# I2C_Multiplexer.net
KiCad netlist of a schematic drawn in Altium Designer
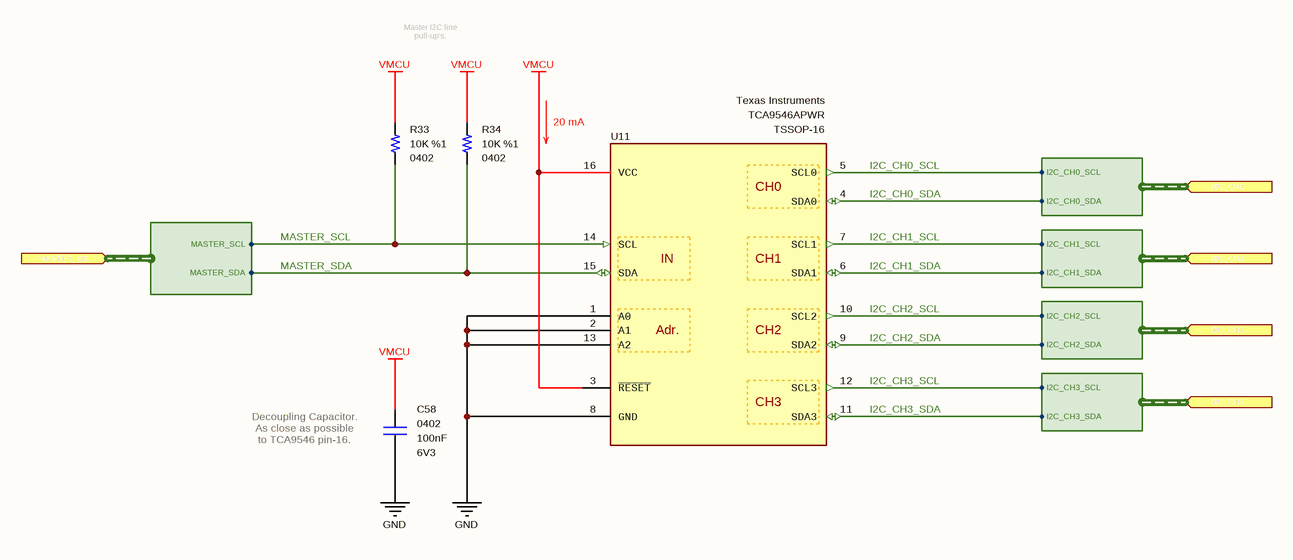
[diagram p0: I2C Multiplexer.SchDoc]

(export (version "E")
  (design (tool "Eeschema 10.0.6"))
  (components
    (comp (ref "C58")
      (value "100nF")
      (footprint "CAPACITOR_0402")
      (description "Capacitor - 100nF [0402-6V3] (Ceramic)")
      (fields
        (field (name "TOLERANCE") "%10")
        (field (name "CASE") "0402")
        (field (name "VOLTAGE") "6V3")
        (field (name "MANUFACTURER PART NUMBER") "04026D104KAT4A")
      )
      (libsource (lib "Ovoo_Library") (part "Capacitor - 100nF [0402-6V3]"))
    )
    (comp (ref "R33")
      (value "10K")
      (footprint "RESISTOR_0402")
      (description "Thick Film Resistors - SMD 1/16 W 10 Kohms 1%")
      (fields
        (field (name "TOLERANCE") "%1")
        (field (name "CASE") "0402")
        (field (name "MANUFACTURER PART NUMBER") "CRCW040210K0FKED")
        (field (name "MOUSER PART NUMBER") "71-CRCW0402-10K-E3")
      )
      (libsource (lib "Ovoo_Library") (part "Resistor - 10K"))
    )
    (comp (ref "R34")
      (value "10K")
      (footprint "RESISTOR_0402")
      (description "Thick Film Resistors - SMD 1/16 W 10 Kohms 1%")
      (fields
        (field (name "TOLERANCE") "%1")
        (field (name "CASE") "0402")
        (field (name "MANUFACTURER PART NUMBER") "CRCW040210K0FKED")
        (field (name "MOUSER PART NUMBER") "71-CRCW0402-10K-E3")
      )
      (libsource (lib "Ovoo_Library") (part "Resistor - 10K"))
    )
    (comp (ref "U11")
      (value "I2C Switch IC")
      (footprint "TSSOP-16")
      (description "Switch ICs - Various 4-Channel I2C and SMBus")
      (fields
        (field (name "MOUSER PART NUMBER") "595-TCA9546APWR")
        (field (name "CASE") "TSSOP-16")
        (field (name "MANUFACTURER PART NUMBER") "TCA9546APWR")
        (field (name "MANUFACTURER NAME") "Texas Instruments")
      )
      (libsource (lib "Ovoo_Library") (part "IC - TCA9546APWR"))
    )
  )
  (nets
    (net (code "6") (name "/I2C_CH0_SCL") (class "Default")
      (node (ref "U11") (pin "5") (pinfunction "SCL0_5") (pintype "output"))
    )
    (net (code "7") (name "/I2C_CH0_SDA") (class "Default")
      (node (ref "U11") (pin "4") (pinfunction "SDA0_4") (pintype "bidirectional"))
    )
    (net (code "8") (name "/I2C_CH1_SCL") (class "Default")
      (node (ref "U11") (pin "7") (pinfunction "SCL1_7") (pintype "output"))
    )
    (net (code "9") (name "/I2C_CH1_SDA") (class "Default")
      (node (ref "U11") (pin "6") (pinfunction "SDA1_6") (pintype "bidirectional"))
    )
    (net (code "10") (name "/I2C_CH2_SCL") (class "Default")
      (node (ref "U11") (pin "10") (pinfunction "SCL2_10") (pintype "output"))
    )
    (net (code "11") (name "/I2C_CH2_SDA") (class "Default")
      (node (ref "U11") (pin "9") (pinfunction "SDA2_9") (pintype "bidirectional"))
    )
    (net (code "12") (name "/I2C_CH3_SCL") (class "Default")
      (node (ref "U11") (pin "12") (pinfunction "SCL3_12") (pintype "output"))
    )
    (net (code "13") (name "/I2C_CH3_SDA") (class "Default")
      (node (ref "U11") (pin "11") (pinfunction "SDA3_11") (pintype "bidirectional"))
    )
    (net (code "14") (name "/MASTER_SCL") (class "Default")
      (node (ref "R33") (pin "1") (pinfunction "1_1") (pintype "passive"))
      (node (ref "U11") (pin "14") (pinfunction "SCL_14") (pintype "input"))
    )
    (net (code "15") (name "/MASTER_SDA") (class "Default")
      (node (ref "R34") (pin "1") (pinfunction "1_1") (pintype "passive"))
      (node (ref "U11") (pin "15") (pinfunction "SDA_15") (pintype "bidirectional"))
    )
    (net (code "21") (name "GND") (class "Default")
      (node (ref "C58") (pin "1") (pinfunction "1_1") (pintype "passive"))
      (node (ref "U11") (pin "1") (pinfunction "A0_1") (pintype "passive"))
      (node (ref "U11") (pin "13") (pinfunction "A2_13") (pintype "passive"))
      (node (ref "U11") (pin "2") (pinfunction "A1_2") (pintype "passive"))
      (node (ref "U11") (pin "8") (pinfunction "GND_8") (pintype "power_in"))
    )
    (net (code "22") (name "VMCU") (class "Default")
      (node (ref "C58") (pin "2") (pinfunction "2_2") (pintype "passive"))
      (node (ref "R33") (pin "2") (pinfunction "2_2") (pintype "passive"))
      (node (ref "R34") (pin "2") (pinfunction "2_2") (pintype "passive"))
      (node (ref "U11") (pin "16") (pinfunction "VCC_16") (pintype "power_in"))
      (node (ref "U11") (pin "3") (pinfunction "~{RESET}_3") (pintype "power_in"))
    )
  )
)
